# sha2017_rev0_1_dev_Kopie.net
KiCad netlist of a schematic drawn in EAGLE
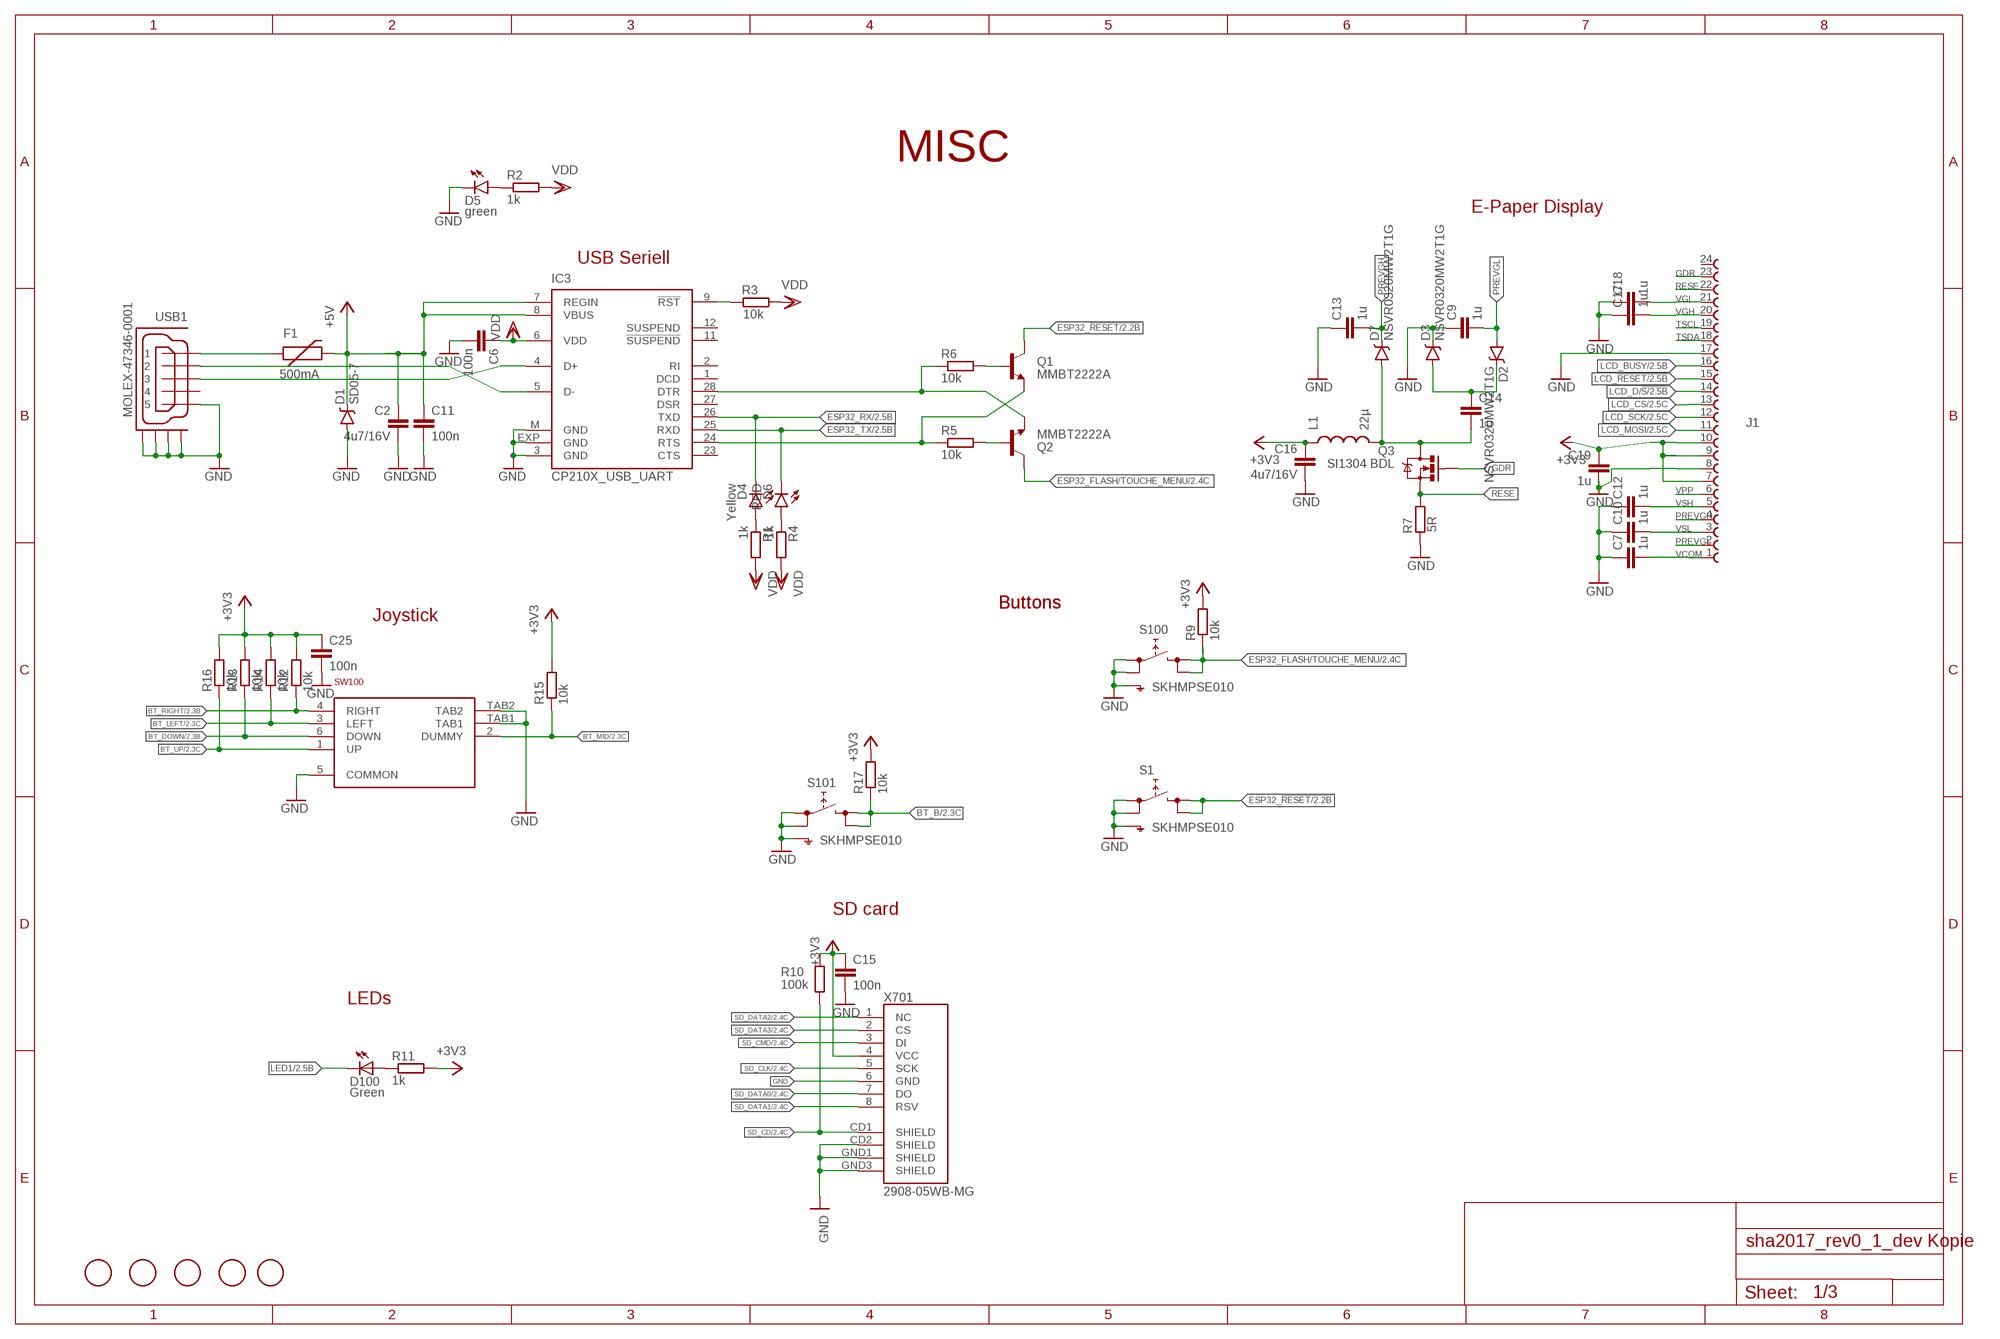
[diagram p0: schematic, sheet 1]
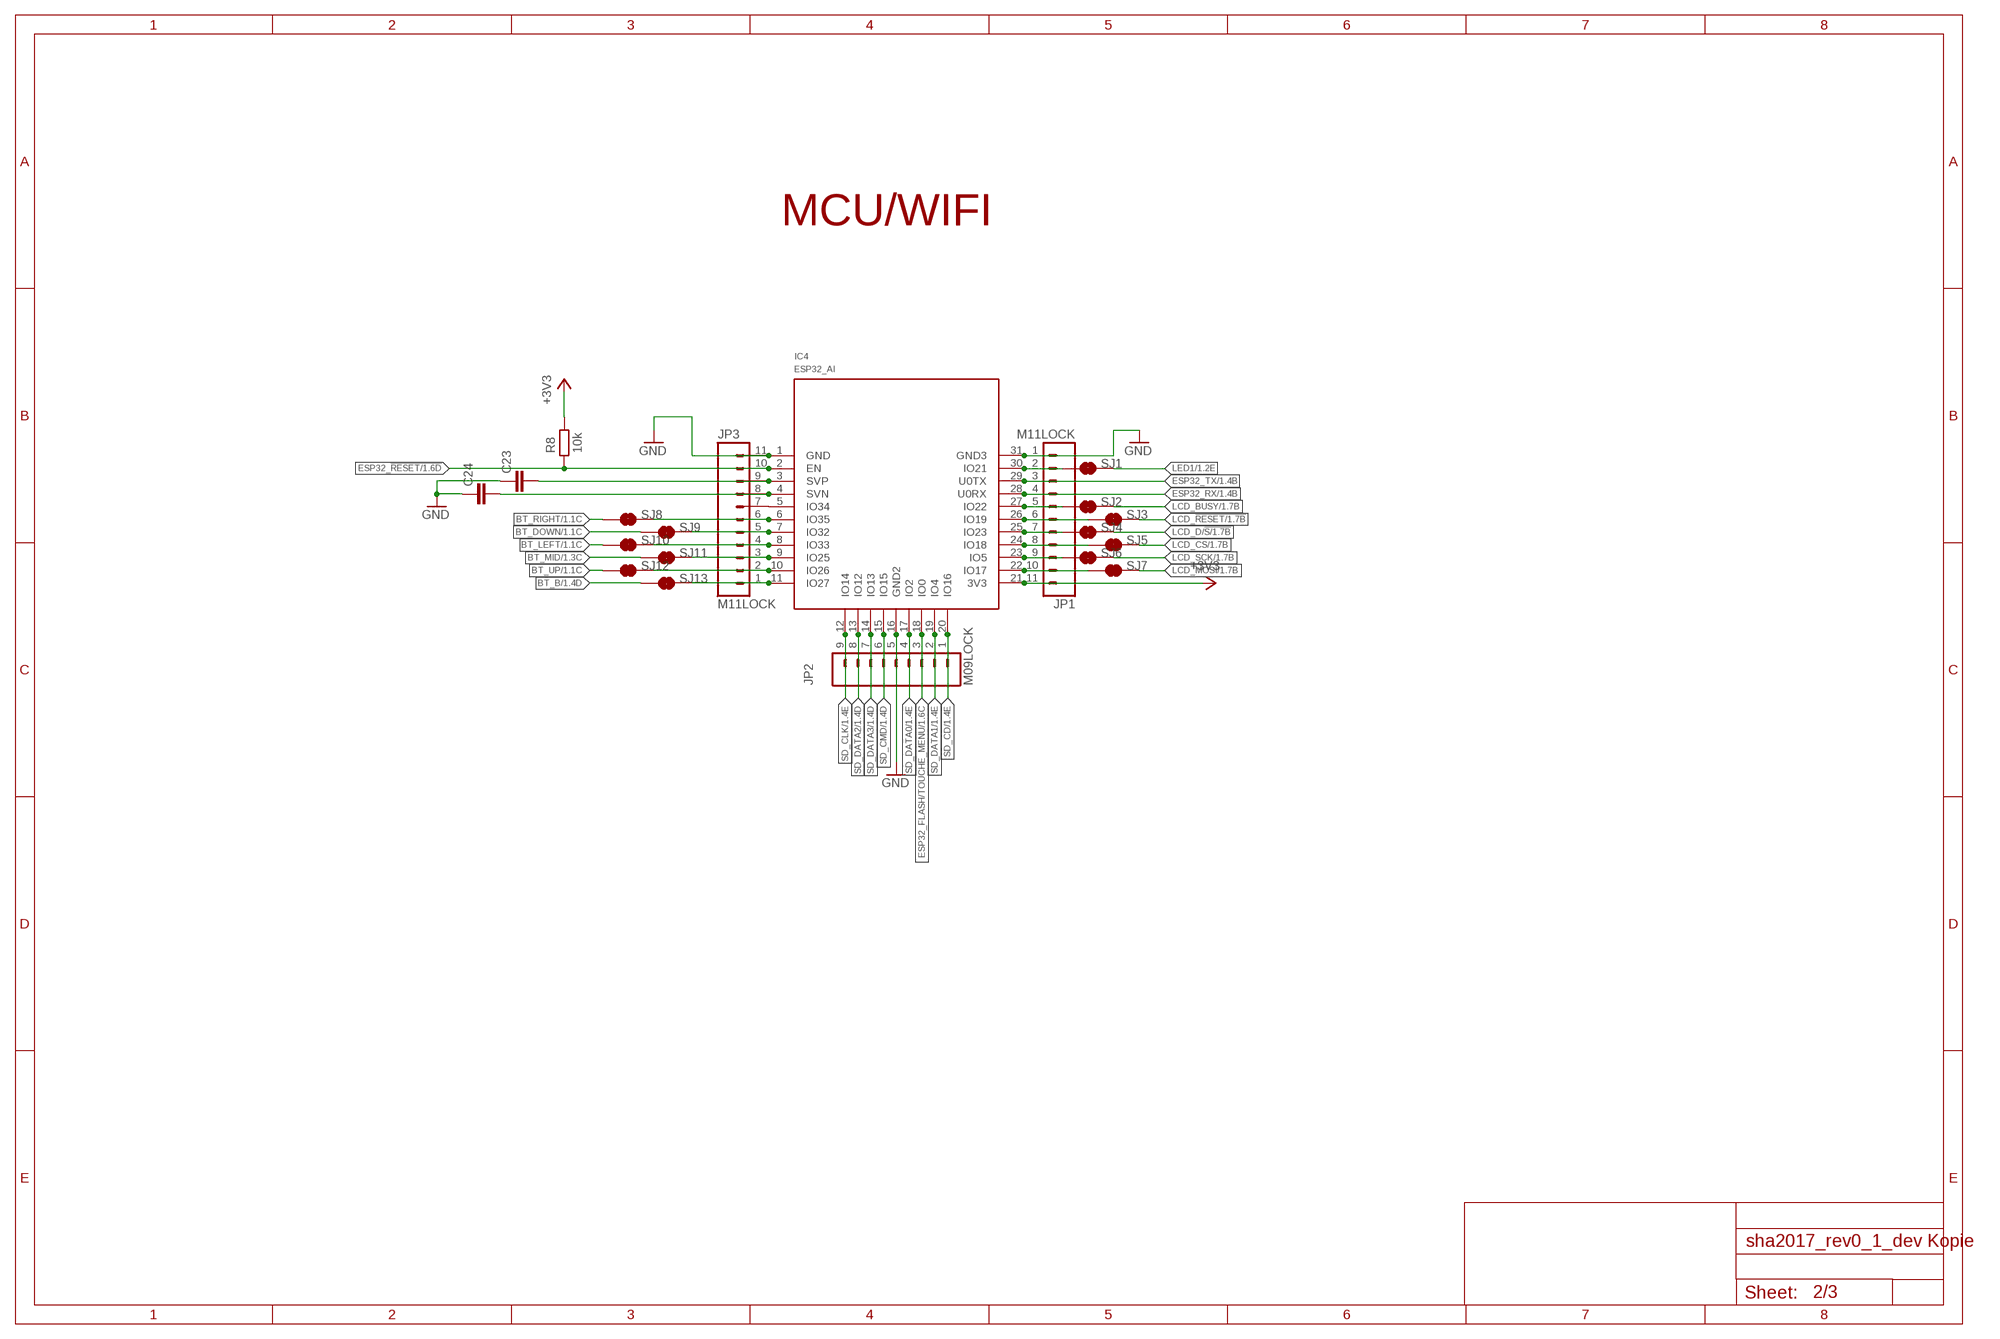
[diagram p1: schematic, sheet 2]
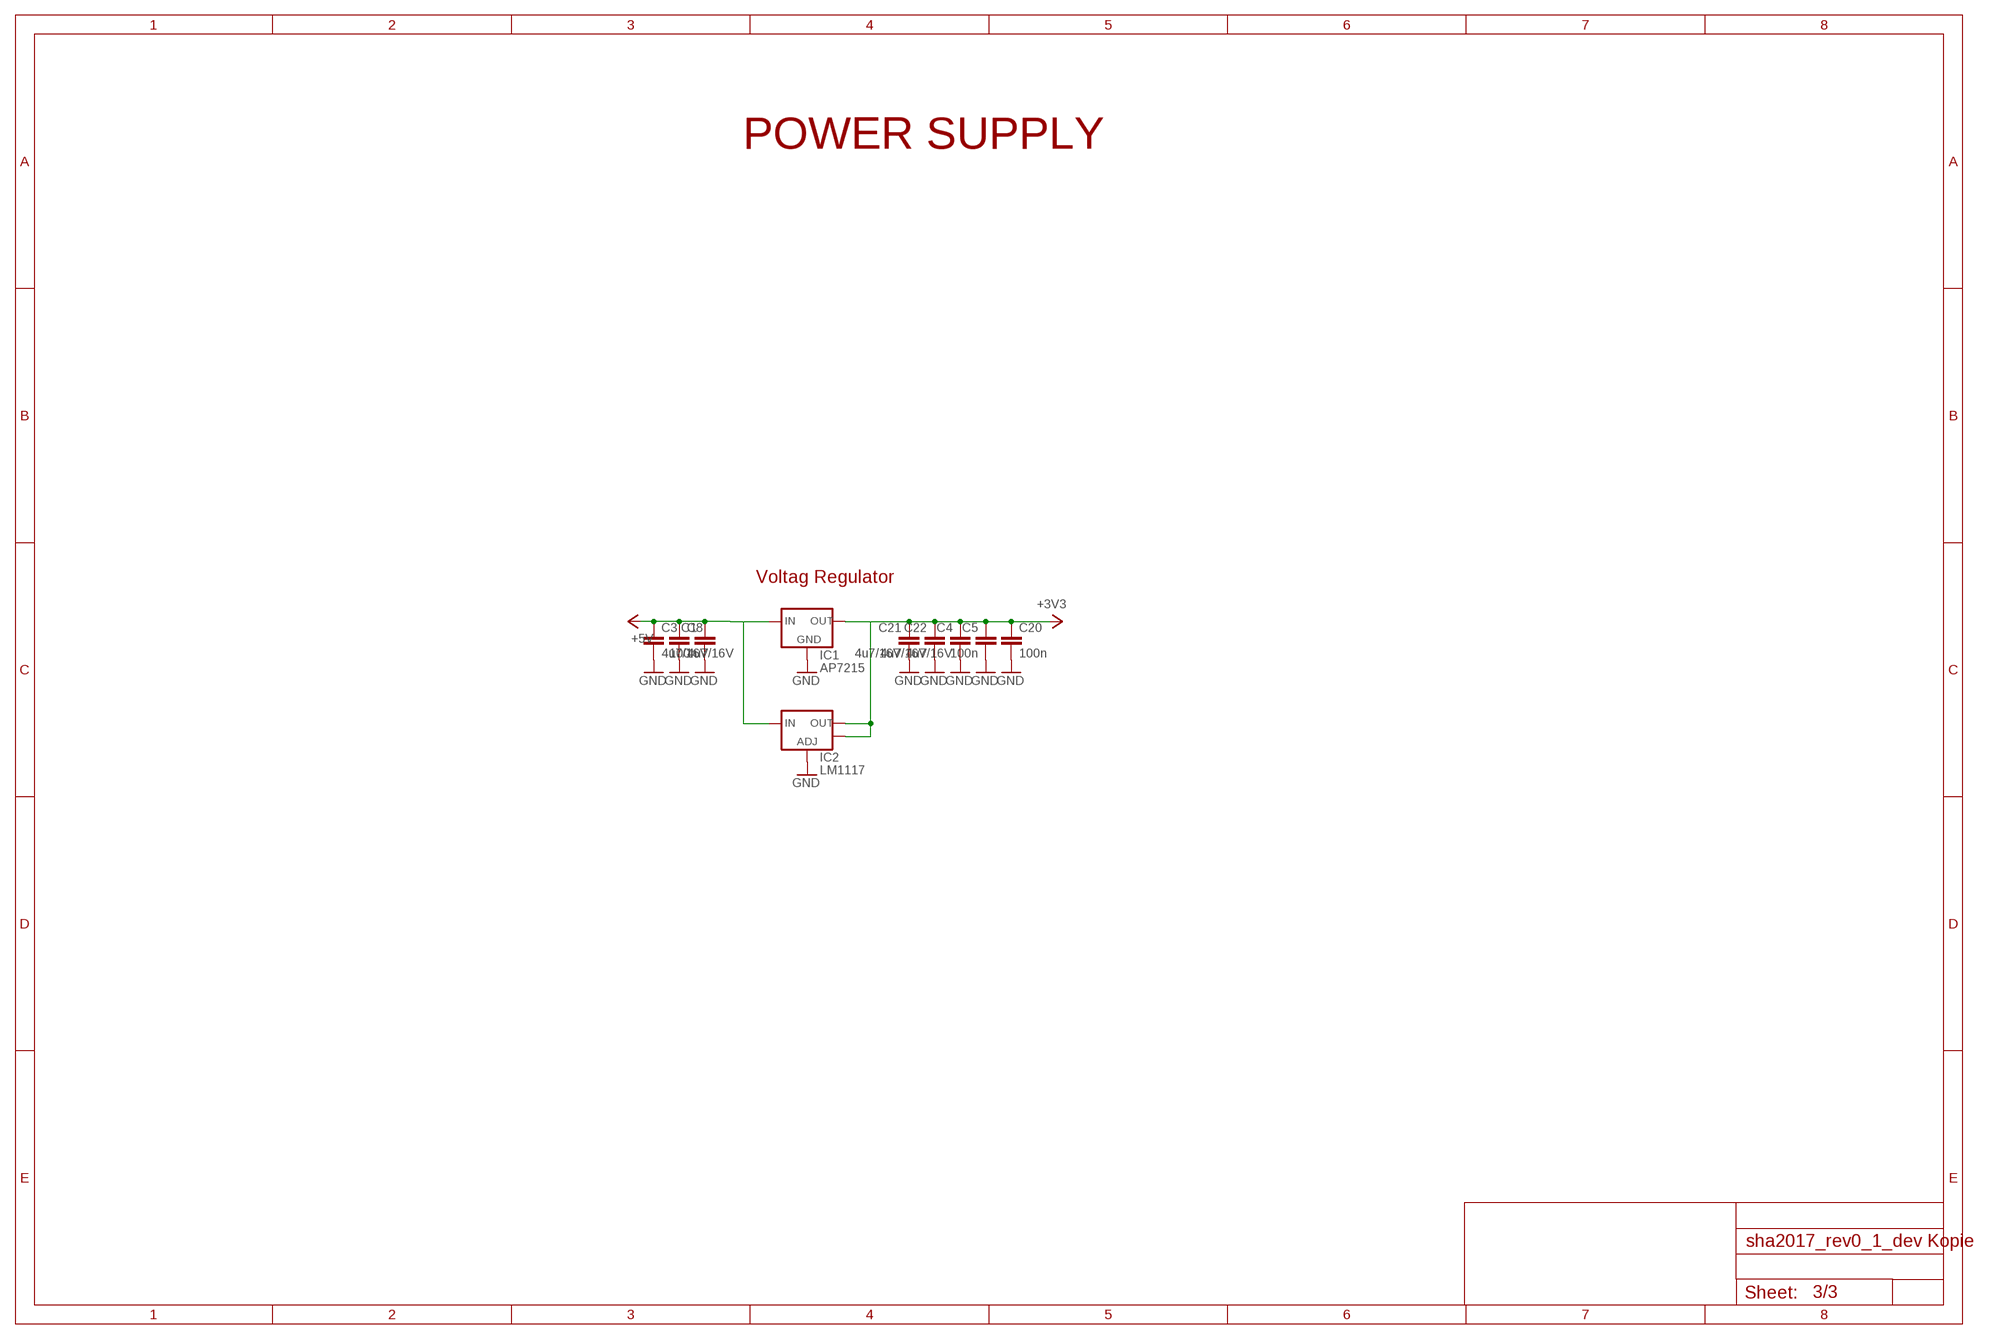
[diagram p2: schematic, sheet 3]

(export (version "E")
  (design (tool "Eeschema 10.0.6"))
  (components
    (comp (ref "C23")
      (value "C-EUC0603")
      (footprint "eagle-import:C0603")
      (libsource (lib "eagle-import") (part "C-EUC0603"))
    )
    (comp (ref "C24")
      (value "C-EUC0603")
      (footprint "eagle-import:C0603")
      (libsource (lib "eagle-import") (part "C-EUC0603"))
    )
    (comp (ref "IC4")
      (value "ESP32_AI")
      (footprint "eagle-import:ESP32_AI")
      (libsource (lib "eagle-import") (part "ESP32_AI"))
    )
    (comp (ref "JP1")
      (value "M11LOCK")
      (footprint "eagle-import:1X11_LOCK")
      (libsource (lib "eagle-import") (part "M11LOCK"))
    )
    (comp (ref "JP2")
      (value "M09LOCK")
      (footprint "eagle-import:1X09_LOCK")
      (libsource (lib "eagle-import") (part "M09LOCK"))
    )
    (comp (ref "JP3")
      (value "M11LOCK")
      (footprint "eagle-import:1X11_LOCK")
      (libsource (lib "eagle-import") (part "M11LOCK"))
    )
    (comp (ref "R8")
      (value "10k")
      (footprint "eagle-import:R0603")
      (fields (field (name "PARTNO") "ERJ-3GEYJ103V"))
      (libsource (lib "eagle-import") (part "R-EU_R0603"))
    )
    (comp (ref "SJ1")
      (value "JUMPER-PAD-2-NC_BY_TRACE")
      (footprint "eagle-import:PAD-JUMPER-2-NC_BY_TRACE_YES_SILK")
      (libsource (lib "eagle-import") (part "JUMPER-PAD-2-NC_BY_TRACE"))
    )
    (comp (ref "SJ2")
      (value "JUMPER-PAD-2-NC_BY_TRACE")
      (footprint "eagle-import:PAD-JUMPER-2-NC_BY_TRACE_YES_SILK")
      (libsource (lib "eagle-import") (part "JUMPER-PAD-2-NC_BY_TRACE"))
    )
    (comp (ref "SJ3")
      (value "JUMPER-PAD-2-NC_BY_TRACE")
      (footprint "eagle-import:PAD-JUMPER-2-NC_BY_TRACE_YES_SILK")
      (libsource (lib "eagle-import") (part "JUMPER-PAD-2-NC_BY_TRACE"))
    )
    (comp (ref "SJ4")
      (value "JUMPER-PAD-2-NC_BY_TRACE")
      (footprint "eagle-import:PAD-JUMPER-2-NC_BY_TRACE_YES_SILK")
      (libsource (lib "eagle-import") (part "JUMPER-PAD-2-NC_BY_TRACE"))
    )
    (comp (ref "SJ5")
      (value "JUMPER-PAD-2-NC_BY_TRACE")
      (footprint "eagle-import:PAD-JUMPER-2-NC_BY_TRACE_YES_SILK")
      (libsource (lib "eagle-import") (part "JUMPER-PAD-2-NC_BY_TRACE"))
    )
    (comp (ref "SJ6")
      (value "JUMPER-PAD-2-NC_BY_TRACE")
      (footprint "eagle-import:PAD-JUMPER-2-NC_BY_TRACE_YES_SILK")
      (libsource (lib "eagle-import") (part "JUMPER-PAD-2-NC_BY_TRACE"))
    )
    (comp (ref "SJ7")
      (value "JUMPER-PAD-2-NC_BY_TRACE")
      (footprint "eagle-import:PAD-JUMPER-2-NC_BY_TRACE_YES_SILK")
      (libsource (lib "eagle-import") (part "JUMPER-PAD-2-NC_BY_TRACE"))
    )
    (comp (ref "SJ8")
      (value "JUMPER-PAD-2-NC_BY_TRACE")
      (footprint "eagle-import:PAD-JUMPER-2-NC_BY_TRACE_YES_SILK")
      (libsource (lib "eagle-import") (part "JUMPER-PAD-2-NC_BY_TRACE"))
    )
    (comp (ref "SJ9")
      (value "JUMPER-PAD-2-NC_BY_TRACE")
      (footprint "eagle-import:PAD-JUMPER-2-NC_BY_TRACE_YES_SILK")
      (libsource (lib "eagle-import") (part "JUMPER-PAD-2-NC_BY_TRACE"))
    )
    (comp (ref "SJ10")
      (value "JUMPER-PAD-2-NC_BY_TRACE")
      (footprint "eagle-import:PAD-JUMPER-2-NC_BY_TRACE_YES_SILK")
      (libsource (lib "eagle-import") (part "JUMPER-PAD-2-NC_BY_TRACE"))
    )
    (comp (ref "SJ11")
      (value "JUMPER-PAD-2-NC_BY_TRACE")
      (footprint "eagle-import:PAD-JUMPER-2-NC_BY_TRACE_YES_SILK")
      (libsource (lib "eagle-import") (part "JUMPER-PAD-2-NC_BY_TRACE"))
    )
    (comp (ref "SJ12")
      (value "JUMPER-PAD-2-NC_BY_TRACE")
      (footprint "eagle-import:PAD-JUMPER-2-NC_BY_TRACE_YES_SILK")
      (libsource (lib "eagle-import") (part "JUMPER-PAD-2-NC_BY_TRACE"))
    )
    (comp (ref "SJ13")
      (value "JUMPER-PAD-2-NC_BY_TRACE")
      (footprint "eagle-import:PAD-JUMPER-2-NC_BY_TRACE_YES_SILK")
      (libsource (lib "eagle-import") (part "JUMPER-PAD-2-NC_BY_TRACE"))
    )
    (comp (ref "C2")
      (value "4u7/16V")
      (footprint "eagle-import:C0805")
      (fields (field (name "PARTNO") "GRM21BR61C475KA88K"))
      (libsource (lib "eagle-import") (part "C-EUC0805"))
    )
    (comp (ref "C6")
      (value "100n")
      (footprint "eagle-import:C0603")
      (fields (field (name "PARTNO") "GRM188R71H104KA93D"))
      (libsource (lib "eagle-import") (part "C-EUC0603"))
    )
    (comp (ref "C7")
      (value "1u")
      (footprint "eagle-import:C0603")
      (fields (field (name "PARTNO") "GRM188R61E105KA12D"))
      (libsource (lib "eagle-import") (part "C-EUC0603"))
    )
    (comp (ref "C9")
      (value "1u")
      (footprint "eagle-import:C0603")
      (fields (field (name "PARTNO") "GRM188R61E105KA12D"))
      (libsource (lib "eagle-import") (part "C-EUC0603"))
    )
    (comp (ref "C10")
      (value "1u")
      (footprint "eagle-import:C0603")
      (fields (field (name "PARTNO") "GRM188R61E105KA12D"))
      (libsource (lib "eagle-import") (part "C-EUC0603"))
    )
    (comp (ref "C11")
      (value "100n")
      (footprint "eagle-import:C0603")
      (fields (field (name "PARTNO") "GRM188R71H104KA93D"))
      (libsource (lib "eagle-import") (part "C-EUC0603"))
    )
    (comp (ref "C12")
      (value "1u")
      (footprint "eagle-import:C0603")
      (fields (field (name "PARTNO") "GRM188R61E105KA12D"))
      (libsource (lib "eagle-import") (part "C-EUC0603"))
    )
    (comp (ref "C13")
      (value "1u")
      (footprint "eagle-import:C0603")
      (fields (field (name "PARTNO") "GRM188R61E105KA12D"))
      (libsource (lib "eagle-import") (part "C-EUC0603"))
    )
    (comp (ref "C14")
      (value "1u")
      (footprint "eagle-import:C0603")
      (fields (field (name "PARTNO") "GRM188R61E105KA12D"))
      (libsource (lib "eagle-import") (part "C-EUC0603"))
    )
    (comp (ref "C15")
      (value "100n")
      (footprint "eagle-import:C0603")
      (fields (field (name "PARTNO") "GRM188R71H104KA93D"))
      (libsource (lib "eagle-import") (part "C-EUC0603"))
    )
    (comp (ref "C16")
      (value "4u7/16V")
      (footprint "eagle-import:C0805")
      (fields (field (name "PARTNO") "GRM21BR61C475KA88K"))
      (libsource (lib "eagle-import") (part "C-EUC0805"))
    )
    (comp (ref "C17")
      (value "1u")
      (footprint "eagle-import:C0603")
      (fields (field (name "PARTNO") "GRM188R61E105KA12D"))
      (libsource (lib "eagle-import") (part "C-EUC0603"))
    )
    (comp (ref "C18")
      (value "1u")
      (footprint "eagle-import:C0603")
      (fields (field (name "PARTNO") "GRM188R61E105KA12D"))
      (libsource (lib "eagle-import") (part "C-EUC0603"))
    )
    (comp (ref "C19")
      (value "1u")
      (footprint "eagle-import:C0603")
      (fields (field (name "PARTNO") "GRM188R61E105KA12D"))
      (libsource (lib "eagle-import") (part "C-EUC0603"))
    )
    (comp (ref "C25")
      (value "100n")
      (footprint "eagle-import:C0603")
      (fields (field (name "PARTNO") "GRM188R71H104KA93D"))
      (libsource (lib "eagle-import") (part "C-EUC0603"))
    )
    (comp (ref "D1")
      (value "SD05-7")
      (footprint "eagle-import:SOD-323")
      (fields (field (name "PARTNO") "PMEG4005EJ,115"))
      (libsource (lib "eagle-import") (part "DIODE-SCHOTTKY-PMEG4005EJ"))
    )
    (comp (ref "D2")
      (value "NSVR0320MW2T1G")
      (footprint "eagle-import:SOD-323")
      (fields (field (name "PARTNO") "BAT20JFILM"))
      (libsource (lib "eagle-import") (part "BAT20JFILM"))
    )
    (comp (ref "D3")
      (value "NSVR0320MW2T1G")
      (footprint "eagle-import:SOD-323")
      (fields (field (name "PARTNO") "BAT20JFILM"))
      (libsource (lib "eagle-import") (part "BAT20JFILM"))
    )
    (comp (ref "D4")
      (value "Yellow")
      (footprint "eagle-import:LED-0603")
      (libsource (lib "eagle-import") (part "LED0603"))
    )
    (comp (ref "D5")
      (value "green")
      (footprint "eagle-import:LED-0603")
      (libsource (lib "eagle-import") (part "LED0603"))
    )
    (comp (ref "D6")
      (value "RED")
      (footprint "eagle-import:LED-0603")
      (libsource (lib "eagle-import") (part "LED0603"))
    )
    (comp (ref "D7")
      (value "NSVR0320MW2T1G")
      (footprint "eagle-import:SOD-323")
      (fields (field (name "PARTNO") "BAT20JFILM"))
      (libsource (lib "eagle-import") (part "BAT20JFILM"))
    )
    (comp (ref "D100")
      (value "Green")
      (footprint "eagle-import:SML1206")
      (fields (field (name "PARTNO") "156120VS75300"))
      (libsource (lib "eagle-import") (part "LEDSML1206"))
    )
    (comp (ref "F1")
      (value "500mA")
      (footprint "eagle-import:PTC-1206")
      (fields (field (name "PARTNO") "0ZCJ0025FF2E"))
      (libsource (lib "eagle-import") (part "PTCSMD"))
    )
    (comp (ref "FD1")
      (value "FIDUCIAL")
      (footprint "eagle-import:FIDUCIAL_1MM")
      (libsource (lib "eagle-import") (part "FIDUCIAL"))
    )
    (comp (ref "FD2")
      (value "FIDUCIAL")
      (footprint "eagle-import:FIDUCIAL_1MM")
      (libsource (lib "eagle-import") (part "FIDUCIAL"))
    )
    (comp (ref "FD3")
      (value "FIDUCIAL")
      (footprint "eagle-import:FIDUCIAL_1MM")
      (libsource (lib "eagle-import") (part "FIDUCIAL"))
    )
    (comp (ref "FD4")
      (value "FIDUCIAL")
      (footprint "eagle-import:FIDUCIAL_1MM")
      (libsource (lib "eagle-import") (part "FIDUCIAL"))
    )
    (comp (ref "FD5")
      (value "FIDUCIAL")
      (footprint "eagle-import:FIDUCIAL_1MM")
      (libsource (lib "eagle-import") (part "FIDUCIAL"))
    )
    (comp (ref "IC3")
      (value "CP210X_USB_UART")
      (footprint "eagle-import:MLP28")
      (fields (field (name "PARTNO") "CP2102-GMR"))
      (libsource (lib "eagle-import") (part "CP210X_USB_UART"))
    )
    (comp (ref "J1")
      (value "68712414022")
      (footprint "eagle-import:68712414022")
      (libsource (lib "eagle-import") (part "68712414022"))
    )
    (comp (ref "L1")
      (value "22µ")
      (footprint "eagle-import:1210")
      (fields (field (name "PARTNO") "NLCV32T-220K-EF"))
      (libsource (lib "eagle-import") (part "INDUCTOR1210"))
    )
    (comp (ref "Q1")
      (value "MMBT2222A")
      (footprint "eagle-import:SOT23-3")
      (fields (field (name "PARTNO") "BC817-25,215"))
      (libsource (lib "eagle-import") (part "TRANSISTOR_NPNMMBT2222A"))
    )
    (comp (ref "Q2")
      (value "MMBT2222A")
      (footprint "eagle-import:SOT23-3")
      (fields (field (name "PARTNO") "BC817-25,215"))
      (libsource (lib "eagle-import") (part "TRANSISTOR_NPNMMBT2222A"))
    )
    (comp (ref "Q3")
      (value "SI1304 BDL")
      (footprint "eagle-import:SOT323")
      (fields (field (name "PARTNO") "SI1308EDL-T1-GE3"))
      (libsource (lib "eagle-import") (part "MOSFET-NCHANNEL2N7002PW"))
    )
    (comp (ref "R1")
      (value "1k")
      (footprint "eagle-import:R0603")
      (fields (field (name "PARTNO") "ERJ-3GEYJ102V"))
      (libsource (lib "eagle-import") (part "R-EU_R0603"))
    )
    (comp (ref "R2")
      (value "1k")
      (footprint "eagle-import:R0603")
      (fields (field (name "PARTNO") "ERJ-3GEYJ102V"))
      (libsource (lib "eagle-import") (part "R-EU_R0603"))
    )
    (comp (ref "R3")
      (value "10k")
      (footprint "eagle-import:R0603")
      (fields (field (name "PARTNO") "ERJ-3GEYJ103V"))
      (libsource (lib "eagle-import") (part "R-EU_R0603"))
    )
    (comp (ref "R4")
      (value "1k")
      (footprint "eagle-import:R0603")
      (fields (field (name "PARTNO") "ERJ-3GEYJ102V"))
      (libsource (lib "eagle-import") (part "R-EU_R0603"))
    )
    (comp (ref "R5")
      (value "10k")
      (footprint "eagle-import:R0603")
      (fields (field (name "PARTNO") "ERJ-3GEYJ103V"))
      (libsource (lib "eagle-import") (part "R-EU_R0603"))
    )
    (comp (ref "R6")
      (value "10k")
      (footprint "eagle-import:R0603")
      (fields (field (name "PARTNO") "ERJ-3GEYJ103V"))
      (libsource (lib "eagle-import") (part "R-EU_R0603"))
    )
    (comp (ref "R7")
      (value "5R")
      (footprint "eagle-import:R0603-DASHES")
      (fields (field (name "PARTNO") "ERJ-3GEYJ5R1V"))
      (libsource (lib "eagle-import") (part "R0603-DASHES"))
    )
    (comp (ref "R9")
      (value "10k")
      (footprint "eagle-import:R0603")
      (fields (field (name "PARTNO") "ERJ-3GEYJ103V"))
      (libsource (lib "eagle-import") (part "R-EU_R0603"))
    )
    (comp (ref "R10")
      (value "100k")
      (footprint "eagle-import:R0603")
      (fields (field (name "PARTNO") "CRCW0603100KFKEA"))
      (libsource (lib "eagle-import") (part "R-EU_R0603"))
    )
    (comp (ref "R11")
      (value "1k")
      (footprint "eagle-import:R0603")
      (fields (field (name "PARTNO") "ERJ-3GEYJ102V"))
      (libsource (lib "eagle-import") (part "R-EU_R0603"))
    )
    (comp (ref "R12")
      (value "10k")
      (footprint "eagle-import:R0603")
      (fields (field (name "PARTNO") "ERJ-3GEYJ103V"))
      (libsource (lib "eagle-import") (part "R-EU_R0603"))
    )
    (comp (ref "R13")
      (value "10k")
      (footprint "eagle-import:R0603")
      (fields (field (name "PARTNO") "ERJ-3GEYJ103V"))
      (libsource (lib "eagle-import") (part "R-EU_R0603"))
    )
    (comp (ref "R14")
      (value "10k")
      (footprint "eagle-import:R0603")
      (fields (field (name "PARTNO") "ERJ-3GEYJ103V"))
      (libsource (lib "eagle-import") (part "R-EU_R0603"))
    )
    (comp (ref "R15")
      (value "10k")
      (footprint "eagle-import:R0603")
      (fields (field (name "PARTNO") "ERJ-3GEYJ103V"))
      (libsource (lib "eagle-import") (part "R-EU_R0603"))
    )
    (comp (ref "R16")
      (value "10k")
      (footprint "eagle-import:R0603")
      (fields (field (name "PARTNO") "ERJ-3GEYJ103V"))
      (libsource (lib "eagle-import") (part "R-EU_R0603"))
    )
    (comp (ref "R17")
      (value "10k")
      (footprint "eagle-import:R0603")
      (fields (field (name "PARTNO") "ERJ-3GEYJ103V"))
      (libsource (lib "eagle-import") (part "R-EU_R0603"))
    )
    (comp (ref "S1")
      (value "SKHMPSE010")
      (footprint "eagle-import:SKHMPXE010")
      (fields (field (name "PARTNO") "SKHMQME010"))
      (libsource (lib "eagle-import") (part "SKHMPE010S"))
    )
    (comp (ref "S100")
      (value "SKHMPSE010")
      (footprint "eagle-import:SKHMPXE010")
      (fields (field (name "PARTNO") "SKHMQME010"))
      (libsource (lib "eagle-import") (part "SKHMPE010S"))
    )
    (comp (ref "S101")
      (value "SKHMPSE010")
      (footprint "eagle-import:SKHMPXE010")
      (fields (field (name "PARTNO") "SKHMQME010"))
      (libsource (lib "eagle-import") (part "SKHMPE010S"))
    )
    (comp (ref "SW100")
      (value "MCMT5-F-V")
      (footprint "eagle-import:MCMT5-F-V")
      (fields (field (name "PARTNO") "SKRHAAE010"))
      (libsource (lib "eagle-import") (part "MCMT5-F-V"))
    )
    (comp (ref "USB1")
      (value "MOLEX-47346-0001")
      (footprint "eagle-import:MOLEX-47364-0001")
      (fields (field (name "PARTNO") "10118194-0001LF"))
      (libsource (lib "eagle-import") (part "MOLEX-47346-0001"))
    )
    (comp (ref "X701")
      (value "2908-05WB-MG")
      (footprint "eagle-import:MICRO-SD-SOCKET-PP")
      (libsource (lib "eagle-import") (part "2908-05WB-MG"))
    )
    (comp (ref "C1")
      (value "100n")
      (footprint "eagle-import:C0603")
      (fields (field (name "PARTNO") "GRM188R71H104KA93D"))
      (libsource (lib "eagle-import") (part "C-EUC0603"))
    )
    (comp (ref "C3")
      (value "4u7/16V")
      (footprint "eagle-import:C0805")
      (fields (field (name "PARTNO") "GRM21BR61C475KA88K"))
      (libsource (lib "eagle-import") (part "C-EUC0805"))
    )
    (comp (ref "C4")
      (value "4u7/16V")
      (footprint "eagle-import:C0805")
      (fields (field (name "PARTNO") "GRM21BR61C475KA88K"))
      (libsource (lib "eagle-import") (part "C-EUC0805"))
    )
    (comp (ref "C5")
      (value "100n")
      (footprint "eagle-import:C0603")
      (fields (field (name "PARTNO") "GRM188R71H104KA93D"))
      (libsource (lib "eagle-import") (part "C-EUC0603"))
    )
    (comp (ref "C8")
      (value "4u7/16V")
      (footprint "eagle-import:C0805")
      (fields (field (name "PARTNO") "GRM21BR61C475KA88K"))
      (libsource (lib "eagle-import") (part "C-EUC0805"))
    )
    (comp (ref "C20")
      (value "100n")
      (footprint "eagle-import:C0603")
      (fields (field (name "PARTNO") "GRM188R71H104KA93D"))
      (libsource (lib "eagle-import") (part "C-EUC0603"))
    )
    (comp (ref "C21")
      (value "4u7/16V")
      (footprint "eagle-import:C0805")
      (fields (field (name "PARTNO") "GRM21BR61C475KA88K"))
      (libsource (lib "eagle-import") (part "C-EUC0805"))
    )
    (comp (ref "C22")
      (value "4u7/16V")
      (footprint "eagle-import:C0805")
      (fields (field (name "PARTNO") "GRM21BR61C475KA88K"))
      (libsource (lib "eagle-import") (part "C-EUC0805"))
    )
    (comp (ref "IC1")
      (value "AP7215")
      (footprint "eagle-import:SOT89")
      (fields (field (name "PARTNO") "AP7215-33YG-13"))
      (libsource (lib "eagle-import") (part "AP7215"))
    )
    (comp (ref "IC2")
      (value "LM1117")
      (footprint "eagle-import:SOT223")
      (fields (field (name "PARTNO") "LM1117MPX-3.3/NOPB"))
      (libsource (lib "eagle-import") (part "V_REG_LM1117SOT223"))
    )
  )
  (nets
    (net (code "1") (name "+3V3") (class "Default")
      (node (ref "C15") (pin "1") (pinfunction "1_1") (pintype "passive"))
      (node (ref "C16") (pin "1") (pinfunction "1_1") (pintype "passive"))
      (node (ref "C19") (pin "1") (pinfunction "1_1") (pintype "passive"))
      (node (ref "C20") (pin "1") (pinfunction "1_1") (pintype "passive"))
      (node (ref "C21") (pin "1") (pinfunction "1_1") (pintype "passive"))
      (node (ref "C22") (pin "1") (pinfunction "1_1") (pintype "passive"))
      (node (ref "C25") (pin "1") (pinfunction "1_1") (pintype "passive"))
      (node (ref "C4") (pin "1") (pinfunction "1_1") (pintype "passive"))
      (node (ref "C5") (pin "1") (pinfunction "1_1") (pintype "passive"))
      (node (ref "IC1") (pin "3") (pinfunction "OUT_3") (pintype "passive"))
      (node (ref "IC2") (pin "2") (pinfunction "OUT_2") (pintype "output"))
      (node (ref "IC2") (pin "4") (pinfunction "OUT_4") (pintype "output"))
      (node (ref "IC4") (pin "21") (pinfunction "3V3_21") (pintype "bidirectional"))
      (node (ref "J1") (pin "10") (pinfunction "10_10") (pintype "passive"))
      (node (ref "J1") (pin "7") (pinfunction "7_7") (pintype "passive"))
      (node (ref "J1") (pin "9") (pinfunction "9_9") (pintype "passive"))
      (node (ref "JP1") (pin "11") (pinfunction "11_11") (pintype "passive"))
      (node (ref "L1") (pin "1") (pinfunction "1_1") (pintype "passive"))
      (node (ref "R10") (pin "1") (pinfunction "1_1") (pintype "passive"))
      (node (ref "R11") (pin "2") (pinfunction "2_2") (pintype "passive"))
      (node (ref "R12") (pin "2") (pinfunction "2_2") (pintype "passive"))
      (node (ref "R13") (pin "2") (pinfunction "2_2") (pintype "passive"))
      (node (ref "R14") (pin "2") (pinfunction "2_2") (pintype "passive"))
      (node (ref "R15") (pin "2") (pinfunction "2_2") (pintype "passive"))
      (node (ref "R16") (pin "2") (pinfunction "2_2") (pintype "passive"))
      (node (ref "R17") (pin "2") (pinfunction "2_2") (pintype "passive"))
      (node (ref "R8") (pin "1") (pinfunction "1_1") (pintype "passive"))
      (node (ref "R9") (pin "2") (pinfunction "2_2") (pintype "passive"))
      (node (ref "X701") (pin "4") (pinfunction "VCC_4") (pintype "bidirectional"))
    )
    (net (code "2") (name "+5V") (class "Default")
      (node (ref "C1") (pin "1") (pinfunction "1_1") (pintype "passive"))
      (node (ref "C11") (pin "1") (pinfunction "1_1") (pintype "passive"))
      (node (ref "C2") (pin "1") (pinfunction "1_1") (pintype "passive"))
      (node (ref "C3") (pin "1") (pinfunction "1_1") (pintype "passive"))
      (node (ref "C8") (pin "1") (pinfunction "1_1") (pintype "passive"))
      (node (ref "D1") (pin "C") (pinfunction "C_C") (pintype "passive"))
      (node (ref "F1") (pin "2") (pinfunction "2_2") (pintype "bidirectional"))
      (node (ref "IC1") (pin "2") (pinfunction "IN_2") (pintype "input"))
      (node (ref "IC1") (pin "2@") (pinfunction "IN_2@") (pintype "input"))
      (node (ref "IC2") (pin "3") (pinfunction "IN_3") (pintype "input"))
      (node (ref "IC3") (pin "7") (pinfunction "REGIN_7") (pintype "passive"))
      (node (ref "IC3") (pin "8") (pinfunction "VBUS_8") (pintype "input"))
    )
    (net (code "3") (name "BT_B") (class "Default")
      (node (ref "R17") (pin "1") (pinfunction "1_1") (pintype "passive"))
      (node (ref "S101") (pin "3") (pinfunction "2.1_3") (pintype "passive"))
      (node (ref "S101") (pin "4") (pinfunction "2.2_4") (pintype "passive"))
      (node (ref "SJ13") (pin "1") (pinfunction "1_1") (pintype "passive"))
    )
    (net (code "4") (name "BT_DOWN") (class "Default")
      (node (ref "R13") (pin "1") (pinfunction "1_1") (pintype "passive"))
      (node (ref "SJ9") (pin "1") (pinfunction "1_1") (pintype "passive"))
      (node (ref "SW100") (pin "6") (pinfunction "DOWN_6") (pintype "bidirectional"))
    )
    (net (code "5") (name "BT_LEFT") (class "Default")
      (node (ref "R14") (pin "1") (pinfunction "1_1") (pintype "passive"))
      (node (ref "SJ10") (pin "1") (pinfunction "1_1") (pintype "passive"))
      (node (ref "SW100") (pin "3") (pinfunction "LEFT_3") (pintype "bidirectional"))
    )
    (net (code "6") (name "BT_MID") (class "Default")
      (node (ref "R15") (pin "1") (pinfunction "1_1") (pintype "passive"))
      (node (ref "SJ11") (pin "1") (pinfunction "1_1") (pintype "passive"))
      (node (ref "SW100") (pin "2") (pinfunction "DUMMY_2") (pintype "bidirectional"))
    )
    (net (code "7") (name "BT_RIGHT") (class "Default")
      (node (ref "R12") (pin "1") (pinfunction "1_1") (pintype "passive"))
      (node (ref "SJ8") (pin "1") (pinfunction "1_1") (pintype "passive"))
      (node (ref "SW100") (pin "4") (pinfunction "RIGHT_4") (pintype "bidirectional"))
    )
    (net (code "8") (name "BT_UP") (class "Default")
      (node (ref "R16") (pin "1") (pinfunction "1_1") (pintype "passive"))
      (node (ref "SJ12") (pin "1") (pinfunction "1_1") (pintype "passive"))
      (node (ref "SW100") (pin "1") (pinfunction "UP_1") (pintype "bidirectional"))
    )
    (net (code "9") (name "ESP32_FLASH{slash}TOUCHE_MENU") (class "Default")
      (node (ref "IC4") (pin "18") (pinfunction "IO0_18") (pintype "bidirectional"))
      (node (ref "JP2") (pin "3") (pinfunction "3_3") (pintype "passive"))
      (node (ref "Q2") (pin "3") (pinfunction "C_3") (pintype "passive"))
      (node (ref "R9") (pin "1") (pinfunction "1_1") (pintype "passive"))
      (node (ref "S100") (pin "3") (pinfunction "2.1_3") (pintype "passive"))
      (node (ref "S100") (pin "4") (pinfunction "2.2_4") (pintype "passive"))
    )
    (net (code "10") (name "ESP32_RX") (class "Default")
      (node (ref "D4") (pin "C") (pinfunction "C_C") (pintype "passive"))
      (node (ref "IC3") (pin "26") (pinfunction "TXD_26") (pintype "output"))
      (node (ref "IC4") (pin "28") (pinfunction "U0RX_28") (pintype "bidirectional"))
      (node (ref "JP1") (pin "4") (pinfunction "4_4") (pintype "passive"))
    )
    (net (code "11") (name "ESP32_TX") (class "Default")
      (node (ref "D6") (pin "C") (pinfunction "C_C") (pintype "passive"))
      (node (ref "IC3") (pin "25") (pinfunction "RXD_25") (pintype "input"))
      (node (ref "IC4") (pin "29") (pinfunction "U0TX_29") (pintype "bidirectional"))
      (node (ref "JP1") (pin "3") (pinfunction "3_3") (pintype "passive"))
    )
    (net (code "12") (name "ESP32_~{RESET}") (class "Default")
      (node (ref "IC4") (pin "2") (pinfunction "EN_2") (pintype "bidirectional"))
      (node (ref "JP3") (pin "10") (pinfunction "10_10") (pintype "passive"))
      (node (ref "Q1") (pin "3") (pinfunction "C_3") (pintype "passive"))
      (node (ref "R8") (pin "2") (pinfunction "2_2") (pintype "passive"))
      (node (ref "S1") (pin "3") (pinfunction "2.1_3") (pintype "passive"))
      (node (ref "S1") (pin "4") (pinfunction "2.2_4") (pintype "passive"))
    )
    (net (code "13") (name "GDR") (class "Default")
      (node (ref "J1") (pin "23") (pinfunction "23_23") (pintype "passive"))
      (node (ref "Q3") (pin "1") (pinfunction "G_1") (pintype "passive"))
    )
    (net (code "14") (name "GND") (class "Default")
      (node (ref "C1") (pin "2") (pinfunction "2_2") (pintype "passive"))
      (node (ref "C10") (pin "1") (pinfunction "1_1") (pintype "passive"))
      (node (ref "C11") (pin "2") (pinfunction "2_2") (pintype "passive"))
      (node (ref "C12") (pin "1") (pinfunction "1_1") (pintype "passive"))
      (node (ref "C13") (pin "1") (pinfunction "1_1") (pintype "passive"))
      (node (ref "C15") (pin "2") (pinfunction "2_2") (pintype "passive"))
      (node (ref "C16") (pin "2") (pinfunction "2_2") (pintype "passive"))
      (node (ref "C17") (pin "1") (pinfunction "1_1") (pintype "passive"))
      (node (ref "C18") (pin "1") (pinfunction "1_1") (pintype "passive"))
      (node (ref "C19") (pin "2") (pinfunction "2_2") (pintype "passive"))
      (node (ref "C2") (pin "2") (pinfunction "2_2") (pintype "passive"))
      (node (ref "C20") (pin "2") (pinfunction "2_2") (pintype "passive"))
      (node (ref "C21") (pin "2") (pinfunction "2_2") (pintype "passive"))
      (node (ref "C22") (pin "2") (pinfunction "2_2") (pintype "passive"))
      (node (ref "C23") (pin "1") (pinfunction "1_1") (pintype "passive"))
      (node (ref "C24") (pin "1") (pinfunction "1_1") (pintype "passive"))
      (node (ref "C25") (pin "2") (pinfunction "2_2") (pintype "passive"))
      (node (ref "C3") (pin "2") (pinfunction "2_2") (pintype "passive"))
      (node (ref "C4") (pin "2") (pinfunction "2_2") (pintype "passive"))
      (node (ref "C5") (pin "2") (pinfunction "2_2") (pintype "passive"))
      (node (ref "C6") (pin "2") (pinfunction "2_2") (pintype "passive"))
      (node (ref "C7") (pin "1") (pinfunction "1_1") (pintype "passive"))
      (node (ref "C8") (pin "2") (pinfunction "2_2") (pintype "passive"))
      (node (ref "C9") (pin "1") (pinfunction "1_1") (pintype "passive"))
      (node (ref "D1") (pin "A") (pinfunction "A_A") (pintype "passive"))
      (node (ref "D3") (pin "C") (pinfunction "C_C") (pintype "passive"))
      (node (ref "D5") (pin "C") (pinfunction "C_C") (pintype "passive"))
      (node (ref "IC1") (pin "1") (pinfunction "GND_1") (pintype "input"))
      (node (ref "IC2") (pin "1") (pinfunction "ADJ_1") (pintype "input"))
      (node (ref "IC3") (pin "3") (pinfunction "GND_3") (pintype "power_in"))
      (node (ref "IC3") (pin "EXP") (pinfunction "GND_EXP") (pintype "power_in"))
      (node (ref "IC3") (pin "M") (pinfunction "GND_M") (pintype "power_in"))
      (node (ref "IC4") (pin "1") (pinfunction "GND_1") (pintype "bidirectional"))
      (node (ref "IC4") (pin "16") (pinfunction "GND2_16") (pintype "bidirectional"))
      (node (ref "IC4") (pin "31") (pinfunction "GND3_31") (pintype "bidirectional"))
      (node (ref "J1") (pin "17") (pinfunction "17_17") (pintype "passive"))
      (node (ref "J1") (pin "8") (pinfunction "8_8") (pintype "passive"))
      (node (ref "JP1") (pin "1") (pinfunction "1_1") (pintype "passive"))
      (node (ref "JP2") (pin "5") (pinfunction "5_5") (pintype "passive"))
      (node (ref "JP3") (pin "11") (pinfunction "11_11") (pintype "passive"))
      (node (ref "R7") (pin "2") (pinfunction "2_2") (pintype "passive"))
      (node (ref "S1") (pin "1") (pinfunction "1.1_1") (pintype "passive"))
      (node (ref "S1") (pin "2") (pinfunction "1.2_2") (pintype "passive"))
      (node (ref "S1") (pin "5") (pinfunction "SH_5") (pintype "passive"))
      (node (ref "S100") (pin "1") (pinfunction "1.1_1") (pintype "passive"))
      (node (ref "S100") (pin "2") (pinfunction "1.2_2") (pintype "passive"))
      (node (ref "S100") (pin "5") (pinfunction "SH_5") (pintype "passive"))
      (node (ref "S101") (pin "1") (pinfunction "1.1_1") (pintype "passive"))
      (node (ref "S101") (pin "2") (pinfunction "1.2_2") (pintype "passive"))
      (node (ref "S101") (pin "5") (pinfunction "SH_5") (pintype "passive"))
      (node (ref "SW100") (pin "5") (pinfunction "COMMON_5") (pintype "bidirectional"))
      (node (ref "SW100") (pin "TAB1") (pinfunction "TAB1_TAB1") (pintype "bidirectional"))
      (node (ref "SW100") (pin "TAB2") (pinfunction "TAB2_TAB2") (pintype "bidirectional"))
      (node (ref "USB1") (pin "5") (pinfunction "5_5") (pintype "input"))
      (node (ref "USB1") (pin "GND1") (pinfunction "GND1_GND1") (pintype "bidirectional"))
      (node (ref "USB1") (pin "GND2") (pinfunction "GND2_GND2") (pintype "bidirectional"))
      (node (ref "USB1") (pin "GND3") (pinfunction "GND3_GND3") (pintype "bidirectional"))
      (node (ref "USB1") (pin "GND4") (pinfunction "GND4_GND4") (pintype "bidirectional"))
      (node (ref "X701") (pin "6") (pinfunction "GND_6") (pintype "bidirectional"))
      (node (ref "X701") (pin "CD2") (pinfunction "SHIELD_CD2") (pintype "bidirectional"))
      (node (ref "X701") (pin "GND1") (pinfunction "SHIELD_GND1") (pintype "bidirectional"))
      (node (ref "X701") (pin "GND3") (pinfunction "SHIELD_GND3") (pintype "bidirectional"))
    )
    (net (code "15") (name "LCD_BUSY") (class "Default")
      (node (ref "J1") (pin "16") (pinfunction "16_16") (pintype "passive"))
      (node (ref "SJ2") (pin "2") (pinfunction "2_2") (pintype "passive"))
    )
    (net (code "16") (name "LCD_CS") (class "Default")
      (node (ref "J1") (pin "13") (pinfunction "13_13") (pintype "passive"))
      (node (ref "SJ5") (pin "2") (pinfunction "2_2") (pintype "passive"))
    )
    (net (code "17") (name "LCD_D{slash}~{S}") (class "Default")
      (node (ref "J1") (pin "14") (pinfunction "14_14") (pintype "passive"))
      (node (ref "SJ4") (pin "2") (pinfunction "2_2") (pintype "passive"))
    )
    (net (code "18") (name "LCD_MOSI") (class "Default")
      (node (ref "J1") (pin "11") (pinfunction "11_11") (pintype "passive"))
      (node (ref "SJ7") (pin "2") (pinfunction "2_2") (pintype "passive"))
    )
    (net (code "19") (name "LCD_SCK") (class "Default")
      (node (ref "J1") (pin "12") (pinfunction "12_12") (pintype "passive"))
      (node (ref "SJ6") (pin "2") (pinfunction "2_2") (pintype "passive"))
    )
    (net (code "20") (name "LCD_~{RESET}") (class "Default")
      (node (ref "J1") (pin "15") (pinfunction "15_15") (pintype "passive"))
      (node (ref "SJ3") (pin "2") (pinfunction "2_2") (pintype "passive"))
    )
    (net (code "21") (name "LED1") (class "Default")
      (node (ref "D100") (pin "C") (pinfunction "C_C") (pintype "passive"))
      (node (ref "SJ1") (pin "2") (pinfunction "2_2") (pintype "passive"))
    )
    (net (code "22") (name "Net-(C14-Pad1)") (class "Default")
      (node (ref "C14") (pin "1") (pinfunction "1_1") (pintype "passive"))
      (node (ref "D2") (pin "C") (pinfunction "C_C") (pintype "passive"))
      (node (ref "D3") (pin "A") (pinfunction "A_A") (pintype "passive"))
    )
    (net (code "23") (name "Net-(D4-PadA)") (class "Default")
      (node (ref "D4") (pin "A") (pinfunction "A_A") (pintype "passive"))
      (node (ref "R1") (pin "1") (pinfunction "1_1") (pintype "passive"))
    )
    (net (code "24") (name "Net-(D5-PadA)") (class "Default")
      (node (ref "D5") (pin "A") (pinfunction "A_A") (pintype "passive"))
      (node (ref "R2") (pin "1") (pinfunction "1_1") (pintype "passive"))
    )
    (net (code "25") (name "Net-(D6-PadA)") (class "Default")
      (node (ref "D6") (pin "A") (pinfunction "A_A") (pintype "passive"))
      (node (ref "R4") (pin "1") (pinfunction "1_1") (pintype "passive"))
    )
    (net (code "26") (name "Net-(D100-PadA)") (class "Default")
      (node (ref "D100") (pin "A") (pinfunction "A_A") (pintype "passive"))
      (node (ref "R11") (pin "1") (pinfunction "1_1") (pintype "passive"))
    )
    (net (code "27") (name "Net-(F1-Pad1)") (class "Default")
      (node (ref "F1") (pin "1") (pinfunction "1_1") (pintype "bidirectional"))
      (node (ref "USB1") (pin "1") (pinfunction "1_1") (pintype "input"))
    )
    (net (code "28") (name "Net-(IC3-D+)") (class "Default")
      (node (ref "IC3") (pin "4") (pinfunction "D+_4") (pintype "bidirectional"))
      (node (ref "USB1") (pin "3") (pinfunction "3_3") (pintype "input"))
    )
    (net (code "29") (name "Net-(IC3-D-)") (class "Default")
      (node (ref "IC3") (pin "5") (pinfunction "D-_5") (pintype "bidirectional"))
      (node (ref "USB1") (pin "2") (pinfunction "2_2") (pintype "input"))
    )
    (net (code "30") (name "Net-(IC3-DTR)") (class "Default")
      (node (ref "IC3") (pin "28") (pinfunction "DTR_28") (pintype "output"))
      (node (ref "Q2") (pin "2") (pinfunction "E_2") (pintype "passive"))
      (node (ref "R6") (pin "1") (pinfunction "1_1") (pintype "passive"))
    )
    (net (code "31") (name "Net-(IC3-RTS)") (class "Default")
      (node (ref "IC3") (pin "24") (pinfunction "RTS_24") (pintype "output"))
      (node (ref "Q1") (pin "2") (pinfunction "E_2") (pintype "passive"))
      (node (ref "R5") (pin "1") (pinfunction "1_1") (pintype "passive"))
    )
    (net (code "32") (name "Net-(IC3-~{RST})") (class "Default")
      (node (ref "IC3") (pin "9") (pinfunction "~{RST}_9") (pintype "bidirectional"))
      (node (ref "R3") (pin "2") (pinfunction "2_2") (pintype "passive"))
    )
    (net (code "33") (name "Net-(IC4-IO5)") (class "Default")
      (node (ref "IC4") (pin "23") (pinfunction "IO5_23") (pintype "bidirectional"))
      (node (ref "JP1") (pin "9") (pinfunction "9_9") (pintype "passive"))
      (node (ref "SJ6") (pin "1") (pinfunction "1_1") (pintype "passive"))
    )
    (net (code "34") (name "Net-(IC4-IO17)") (class "Default")
      (node (ref "IC4") (pin "22") (pinfunction "IO17_22") (pintype "bidirectional"))
      (node (ref "JP1") (pin "10") (pinfunction "10_10") (pintype "passive"))
      (node (ref "SJ7") (pin "1") (pinfunction "1_1") (pintype "passive"))
    )
    (net (code "35") (name "Net-(IC4-IO18)") (class "Default")
      (node (ref "IC4") (pin "24") (pinfunction "IO18_24") (pintype "bidirectional"))
      (node (ref "JP1") (pin "8") (pinfunction "8_8") (pintype "passive"))
      (node (ref "SJ5") (pin "1") (pinfunction "1_1") (pintype "passive"))
    )
    (net (code "36") (name "Net-(IC4-IO19)") (class "Default")
      (node (ref "IC4") (pin "26") (pinfunction "IO19_26") (pintype "bidirectional"))
      (node (ref "JP1") (pin "6") (pinfunction "6_6") (pintype "passive"))
      (node (ref "SJ3") (pin "1") (pinfunction "1_1") (pintype "passive"))
    )
    (net (code "37") (name "Net-(IC4-IO21)") (class "Default")
      (node (ref "IC4") (pin "30") (pinfunction "IO21_30") (pintype "bidirectional"))
      (node (ref "JP1") (pin "2") (pinfunction "2_2") (pintype "passive"))
      (node (ref "SJ1") (pin "1") (pinfunction "1_1") (pintype "passive"))
    )
    (net (code "38") (name "Net-(IC4-IO22)") (class "Default")
      (node (ref "IC4") (pin "27") (pinfunction "IO22_27") (pintype "bidirectional"))
      (node (ref "JP1") (pin "5") (pinfunction "5_5") (pintype "passive"))
      (node (ref "SJ2") (pin "1") (pinfunction "1_1") (pintype "passive"))
    )
    (net (code "39") (name "Net-(IC4-IO23)") (class "Default")
      (node (ref "IC4") (pin "25") (pinfunction "IO23_25") (pintype "bidirectional"))
      (node (ref "JP1") (pin "7") (pinfunction "7_7") (pintype "passive"))
      (node (ref "SJ4") (pin "1") (pinfunction "1_1") (pintype "passive"))
    )
    (net (code "40") (name "Net-(IC4-IO25)") (class "Default")
      (node (ref "IC4") (pin "9") (pinfunction "IO25_9") (pintype "bidirectional"))
      (node (ref "JP3") (pin "3") (pinfunction "3_3") (pintype "passive"))
      (node (ref "SJ11") (pin "2") (pinfunction "2_2") (pintype "passive"))
    )
    (net (code "41") (name "Net-(IC4-IO26)") (class "Default")
      (node (ref "IC4") (pin "10") (pinfunction "IO26_10") (pintype "bidirectional"))
      (node (ref "JP3") (pin "2") (pinfunction "2_2") (pintype "passive"))
      (node (ref "SJ12") (pin "2") (pinfunction "2_2") (pintype "passive"))
    )
    (net (code "42") (name "Net-(IC4-IO27)") (class "Default")
      (node (ref "IC4") (pin "11") (pinfunction "IO27_11") (pintype "bidirectional"))
      (node (ref "JP3") (pin "1") (pinfunction "1_1") (pintype "passive"))
      (node (ref "SJ13") (pin "2") (pinfunction "2_2") (pintype "passive"))
    )
    (net (code "43") (name "Net-(IC4-IO32)") (class "Default")
      (node (ref "IC4") (pin "7") (pinfunction "IO32_7") (pintype "bidirectional"))
      (node (ref "JP3") (pin "5") (pinfunction "5_5") (pintype "passive"))
      (node (ref "SJ9") (pin "2") (pinfunction "2_2") (pintype "passive"))
    )
    (net (code "44") (name "Net-(IC4-IO33)") (class "Default")
      (node (ref "IC4") (pin "8") (pinfunction "IO33_8") (pintype "bidirectional"))
      (node (ref "JP3") (pin "4") (pinfunction "4_4") (pintype "passive"))
      (node (ref "SJ10") (pin "2") (pinfunction "2_2") (pintype "passive"))
    )
    (net (code "45") (name "Net-(IC4-IO34)") (class "Default")
      (node (ref "IC4") (pin "5") (pinfunction "IO34_5") (pintype "bidirectional"))
      (node (ref "JP3") (pin "7") (pinfunction "7_7") (pintype "passive"))
    )
    (net (code "46") (name "Net-(IC4-IO35)") (class "Default")
      (node (ref "IC4") (pin "6") (pinfunction "IO35_6") (pintype "bidirectional"))
      (node (ref "JP3") (pin "6") (pinfunction "6_6") (pintype "passive"))
      (node (ref "SJ8") (pin "2") (pinfunction "2_2") (pintype "passive"))
    )
    (net (code "47") (name "Net-(IC4-SVN)") (class "Default")
      (node (ref "C24") (pin "2") (pinfunction "2_2") (pintype "passive"))
      (node (ref "IC4") (pin "4") (pinfunction "SVN_4") (pintype "bidirectional"))
      (node (ref "JP3") (pin "8") (pinfunction "8_8") (pintype "passive"))
    )
    (net (code "48") (name "Net-(IC4-SVP)") (class "Default")
      (node (ref "C23") (pin "2") (pinfunction "2_2") (pintype "passive"))
      (node (ref "IC4") (pin "3") (pinfunction "SVP_3") (pintype "bidirectional"))
      (node (ref "JP3") (pin "9") (pinfunction "9_9") (pintype "passive"))
    )
    (net (code "49") (name "Net-(Q1-B)") (class "Default")
      (node (ref "Q1") (pin "1") (pinfunction "B_1") (pintype "passive"))
      (node (ref "R6") (pin "2") (pinfunction "2_2") (pintype "passive"))
    )
    (net (code "50") (name "Net-(Q2-B)") (class "Default")
      (node (ref "Q2") (pin "1") (pinfunction "B_1") (pintype "passive"))
      (node (ref "R5") (pin "2") (pinfunction "2_2") (pintype "passive"))
    )
    (net (code "51") (name "Net-(Q3-D)") (class "Default")
      (node (ref "C14") (pin "2") (pinfunction "2_2") (pintype "passive"))
      (node (ref "D7") (pin "A") (pinfunction "A_A") (pintype "passive"))
      (node (ref "L1") (pin "2") (pinfunction "2_2") (pintype "passive"))
      (node (ref "Q3") (pin "3") (pinfunction "D_3") (pintype "passive"))
    )
    (net (code "52") (name "PREVGH") (class "Default")
      (node (ref "C13") (pin "2") (pinfunction "2_2") (pintype "passive"))
      (node (ref "D7") (pin "C") (pinfunction "C_C") (pintype "passive"))
      (node (ref "J1") (pin "4") (pinfunction "4_4") (pintype "passive"))
    )
    (net (code "53") (name "PREVGL") (class "Default")
      (node (ref "C9") (pin "2") (pinfunction "2_2") (pintype "passive"))
      (node (ref "D2") (pin "A") (pinfunction "A_A") (pintype "passive"))
      (node (ref "J1") (pin "2") (pinfunction "2_2") (pintype "passive"))
    )
    (net (code "54") (name "RESE") (class "Default")
      (node (ref "J1") (pin "22") (pinfunction "22_22") (pintype "passive"))
      (node (ref "Q3") (pin "2") (pinfunction "S_2") (pintype "passive"))
      (node (ref "R7") (pin "1") (pinfunction "1_1") (pintype "passive"))
    )
    (net (code "55") (name "SD_CD") (class "Default")
      (node (ref "IC4") (pin "20") (pinfunction "IO16_20") (pintype "bidirectional"))
      (node (ref "JP2") (pin "1") (pinfunction "1_1") (pintype "passive"))
      (node (ref "R10") (pin "2") (pinfunction "2_2") (pintype "passive"))
      (node (ref "X701") (pin "CD1") (pinfunction "SHIELD_CD1") (pintype "bidirectional"))
    )
    (net (code "56") (name "SD_CLK") (class "Default")
      (node (ref "IC4") (pin "12") (pinfunction "IO14_12") (pintype "bidirectional"))
      (node (ref "JP2") (pin "9") (pinfunction "9_9") (pintype "passive"))
      (node (ref "X701") (pin "5") (pinfunction "SCK_5") (pintype "bidirectional"))
    )
    (net (code "57") (name "SD_CMD") (class "Default")
      (node (ref "IC4") (pin "15") (pinfunction "IO15_15") (pintype "bidirectional"))
      (node (ref "JP2") (pin "6") (pinfunction "6_6") (pintype "passive"))
      (node (ref "X701") (pin "3") (pinfunction "DI_3") (pintype "bidirectional"))
    )
    (net (code "58") (name "SD_DATA0") (class "Default")
      (node (ref "IC4") (pin "17") (pinfunction "IO2_17") (pintype "bidirectional"))
      (node (ref "JP2") (pin "4") (pinfunction "4_4") (pintype "passive"))
      (node (ref "X701") (pin "7") (pinfunction "DO_7") (pintype "bidirectional"))
    )
    (net (code "59") (name "SD_DATA1") (class "Default")
      (node (ref "IC4") (pin "19") (pinfunction "IO4_19") (pintype "bidirectional"))
      (node (ref "JP2") (pin "2") (pinfunction "2_2") (pintype "passive"))
      (node (ref "X701") (pin "8") (pinfunction "RSV_8") (pintype "bidirectional"))
    )
    (net (code "60") (name "SD_DATA2") (class "Default")
      (node (ref "IC4") (pin "13") (pinfunction "IO12_13") (pintype "bidirectional"))
      (node (ref "JP2") (pin "8") (pinfunction "8_8") (pintype "passive"))
      (node (ref "X701") (pin "1") (pinfunction "NC_1") (pintype "bidirectional"))
    )
    (net (code "61") (name "SD_DATA3") (class "Default")
      (node (ref "IC4") (pin "14") (pinfunction "IO13_14") (pintype "bidirectional"))
      (node (ref "JP2") (pin "7") (pinfunction "7_7") (pintype "passive"))
      (node (ref "X701") (pin "2") (pinfunction "CS_2") (pintype "bidirectional"))
    )
    (net (code "62") (name "TSCL") (class "Default")
      (node (ref "J1") (pin "19") (pinfunction "19_19") (pintype "passive"))
    )
    (net (code "63") (name "TSDA") (class "Default")
      (node (ref "J1") (pin "18") (pinfunction "18_18") (pintype "passive"))
    )
    (net (code "64") (name "VCOM") (class "Default")
      (node (ref "C7") (pin "2") (pinfunction "2_2") (pintype "passive"))
      (node (ref "J1") (pin "1") (pinfunction "1_1") (pintype "passive"))
    )
    (net (code "65") (name "VDD") (class "Default")
      (node (ref "C6") (pin "1") (pinfunction "1_1") (pintype "passive"))
      (node (ref "IC3") (pin "6") (pinfunction "VDD_6") (pintype "power_in"))
      (node (ref "R1") (pin "2") (pinfunction "2_2") (pintype "passive"))
      (node (ref "R2") (pin "2") (pinfunction "2_2") (pintype "passive"))
      (node (ref "R3") (pin "1") (pinfunction "1_1") (pintype "passive"))
      (node (ref "R4") (pin "2") (pinfunction "2_2") (pintype "passive"))
    )
    (net (code "66") (name "VGH") (class "Default")
      (node (ref "C17") (pin "2") (pinfunction "2_2") (pintype "passive"))
      (node (ref "J1") (pin "20") (pinfunction "20_20") (pintype "passive"))
    )
    (net (code "67") (name "VGL") (class "Default")
      (node (ref "C18") (pin "2") (pinfunction "2_2") (pintype "passive"))
      (node (ref "J1") (pin "21") (pinfunction "21_21") (pintype "passive"))
    )
    (net (code "68") (name "VPP") (class "Default")
      (node (ref "J1") (pin "6") (pinfunction "6_6") (pintype "passive"))
    )
    (net (code "69") (name "VSH") (class "Default")
      (node (ref "C12") (pin "2") (pinfunction "2_2") (pintype "passive"))
      (node (ref "J1") (pin "5") (pinfunction "5_5") (pintype "passive"))
    )
    (net (code "70") (name "VSL") (class "Default")
      (node (ref "C10") (pin "2") (pinfunction "2_2") (pintype "passive"))
      (node (ref "J1") (pin "3") (pinfunction "3_3") (pintype "passive"))
    )
    (net (code "71") (name "unconnected-(IC3-CTS-Pad23)") (class "Default")
      (node (ref "IC3") (pin "23") (pinfunction "CTS_23") (pintype "input"))
    )
    (net (code "72") (name "unconnected-(IC3-DCD-Pad1)") (class "Default")
      (node (ref "IC3") (pin "1") (pinfunction "DCD_1") (pintype "input"))
    )
    (net (code "73") (name "unconnected-(IC3-DSR-Pad27)") (class "Default")
      (node (ref "IC3") (pin "27") (pinfunction "DSR_27") (pintype "input"))
    )
    (net (code "74") (name "unconnected-(IC3-RI-Pad2)") (class "Default")
      (node (ref "IC3") (pin "2") (pinfunction "RI_2") (pintype "input"))
    )
    (net (code "75") (name "unconnected-(IC3-SUSPEND-Pad12)") (class "Default")
      (node (ref "IC3") (pin "12") (pinfunction "SUSPEND_12") (pintype "output"))
    )
    (net (code "76") (name "unconnected-(IC3-~{SUSPEND}-Pad11)") (class "Default")
      (node (ref "IC3") (pin "11") (pinfunction "~{SUSPEND}_11") (pintype "output"))
    )
    (net (code "77") (name "unconnected-(J1-Pad24)") (class "Default")
      (node (ref "J1") (pin "24") (pinfunction "24_24") (pintype "passive"))
    )
    (net (code "78") (name "unconnected-(USB1-Pad4)") (class "Default")
      (node (ref "USB1") (pin "4") (pinfunction "4_4") (pintype "input"))
    )
  )
)
